# GPACConnector.net
KiCad netlist of a schematic drawn in Altium Designer
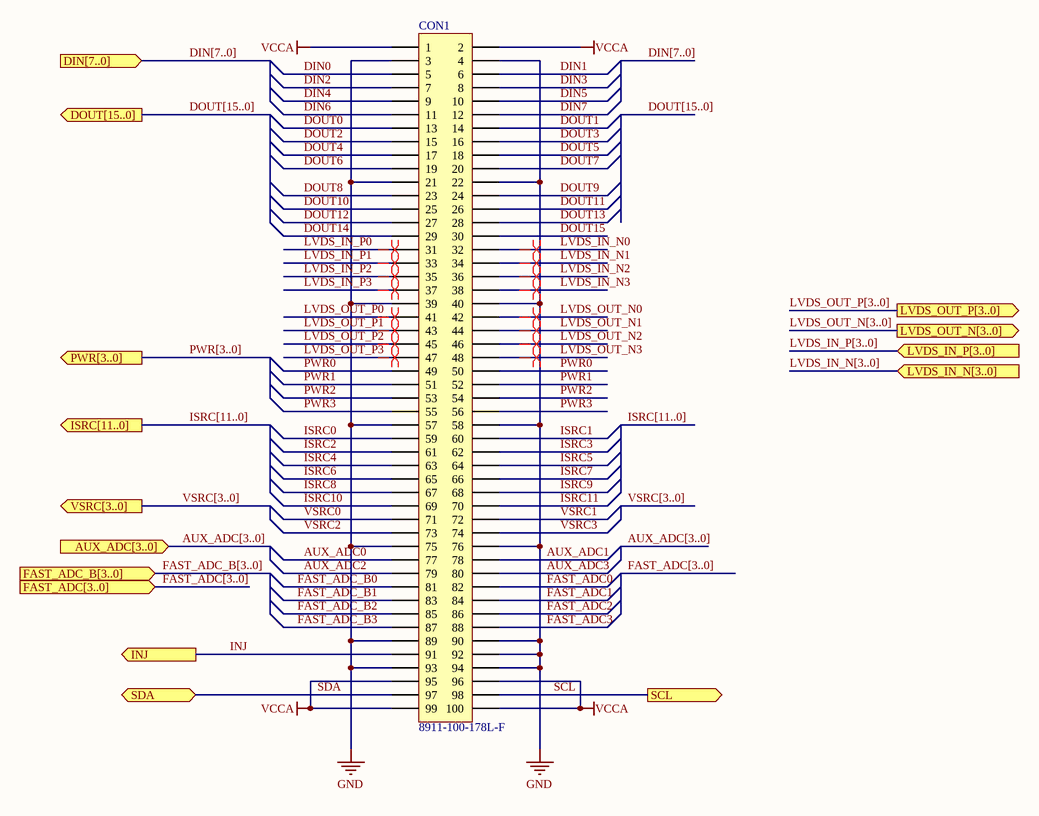
[diagram p0: GPACConnector.SchDoc]

(export (version "E")
  (design (tool "Eeschema 10.0.6"))
  (components
    (comp (ref "CON1")
      (value "-")
      (footprint "KEL 8911-100-178L-F, PLUG")
      (description "KEL 8911 100 pin board to board connector")
      (fields (field (name "TYPE_1") "8911-100-178L-F") (field (name "PUBLISHER") "Silab J.S."))
      (libsource (lib "Silab_Lib") (part "CON KEL 8911, male"))
    )
  )
  (nets
    (net (code "1") (name "/AUX_ADC0") (class "Default")
      (node (ref "CON1") (pin "77") (pinfunction "77_77") (pintype "passive"))
    )
    (net (code "2") (name "/AUX_ADC1") (class "Default")
      (node (ref "CON1") (pin "78") (pinfunction "78_78") (pintype "passive"))
    )
    (net (code "3") (name "/AUX_ADC2") (class "Default")
      (node (ref "CON1") (pin "79") (pinfunction "79_79") (pintype "passive"))
    )
    (net (code "4") (name "/AUX_ADC3") (class "Default")
      (node (ref "CON1") (pin "80") (pinfunction "80_80") (pintype "passive"))
    )
    (net (code "6") (name "/DIN0") (class "Default")
      (node (ref "CON1") (pin "5") (pinfunction "5_5") (pintype "passive"))
    )
    (net (code "7") (name "/DIN1") (class "Default")
      (node (ref "CON1") (pin "6") (pinfunction "6_6") (pintype "passive"))
    )
    (net (code "8") (name "/DIN2") (class "Default")
      (node (ref "CON1") (pin "7") (pinfunction "7_7") (pintype "passive"))
    )
    (net (code "9") (name "/DIN3") (class "Default")
      (node (ref "CON1") (pin "8") (pinfunction "8_8") (pintype "passive"))
    )
    (net (code "10") (name "/DIN4") (class "Default")
      (node (ref "CON1") (pin "9") (pinfunction "9_9") (pintype "passive"))
    )
    (net (code "11") (name "/DIN5") (class "Default")
      (node (ref "CON1") (pin "10") (pinfunction "10_10") (pintype "passive"))
    )
    (net (code "12") (name "/DIN6") (class "Default")
      (node (ref "CON1") (pin "11") (pinfunction "11_11") (pintype "passive"))
    )
    (net (code "13") (name "/DIN7") (class "Default")
      (node (ref "CON1") (pin "12") (pinfunction "12_12") (pintype "passive"))
    )
    (net (code "15") (name "/DOUT0") (class "Default")
      (node (ref "CON1") (pin "13") (pinfunction "13_13") (pintype "passive"))
    )
    (net (code "16") (name "/DOUT1") (class "Default")
      (node (ref "CON1") (pin "14") (pinfunction "14_14") (pintype "passive"))
    )
    (net (code "17") (name "/DOUT2") (class "Default")
      (node (ref "CON1") (pin "15") (pinfunction "15_15") (pintype "passive"))
    )
    (net (code "18") (name "/DOUT3") (class "Default")
      (node (ref "CON1") (pin "16") (pinfunction "16_16") (pintype "passive"))
    )
    (net (code "19") (name "/DOUT4") (class "Default")
      (node (ref "CON1") (pin "17") (pinfunction "17_17") (pintype "passive"))
    )
    (net (code "20") (name "/DOUT5") (class "Default")
      (node (ref "CON1") (pin "18") (pinfunction "18_18") (pintype "passive"))
    )
    (net (code "21") (name "/DOUT6") (class "Default")
      (node (ref "CON1") (pin "19") (pinfunction "19_19") (pintype "passive"))
    )
    (net (code "22") (name "/DOUT7") (class "Default")
      (node (ref "CON1") (pin "20") (pinfunction "20_20") (pintype "passive"))
    )
    (net (code "23") (name "/DOUT8") (class "Default")
      (node (ref "CON1") (pin "23") (pinfunction "23_23") (pintype "passive"))
    )
    (net (code "24") (name "/DOUT9") (class "Default")
      (node (ref "CON1") (pin "24") (pinfunction "24_24") (pintype "passive"))
    )
    (net (code "25") (name "/DOUT10") (class "Default")
      (node (ref "CON1") (pin "25") (pinfunction "25_25") (pintype "passive"))
    )
    (net (code "26") (name "/DOUT11") (class "Default")
      (node (ref "CON1") (pin "26") (pinfunction "26_26") (pintype "passive"))
    )
    (net (code "27") (name "/DOUT12") (class "Default")
      (node (ref "CON1") (pin "27") (pinfunction "27_27") (pintype "passive"))
    )
    (net (code "28") (name "/DOUT13") (class "Default")
      (node (ref "CON1") (pin "28") (pinfunction "28_28") (pintype "passive"))
    )
    (net (code "29") (name "/DOUT14") (class "Default")
      (node (ref "CON1") (pin "29") (pinfunction "29_29") (pintype "passive"))
    )
    (net (code "30") (name "/DOUT15") (class "Default")
      (node (ref "CON1") (pin "30") (pinfunction "30_30") (pintype "passive"))
    )
    (net (code "32") (name "/FAST_ADC0") (class "Default")
      (node (ref "CON1") (pin "82") (pinfunction "82_82") (pintype "passive"))
    )
    (net (code "33") (name "/FAST_ADC1") (class "Default")
      (node (ref "CON1") (pin "84") (pinfunction "84_84") (pintype "passive"))
    )
    (net (code "34") (name "/FAST_ADC2") (class "Default")
      (node (ref "CON1") (pin "86") (pinfunction "86_86") (pintype "passive"))
    )
    (net (code "35") (name "/FAST_ADC3") (class "Default")
      (node (ref "CON1") (pin "88") (pinfunction "88_88") (pintype "passive"))
    )
    (net (code "37") (name "/FAST_ADC_B0") (class "Default")
      (node (ref "CON1") (pin "81") (pinfunction "81_81") (pintype "passive"))
    )
    (net (code "38") (name "/FAST_ADC_B1") (class "Default")
      (node (ref "CON1") (pin "83") (pinfunction "83_83") (pintype "passive"))
    )
    (net (code "39") (name "/FAST_ADC_B2") (class "Default")
      (node (ref "CON1") (pin "85") (pinfunction "85_85") (pintype "passive"))
    )
    (net (code "40") (name "/FAST_ADC_B3") (class "Default")
      (node (ref "CON1") (pin "87") (pinfunction "87_87") (pintype "passive"))
    )
    (net (code "42") (name "/INJ") (class "Default")
      (node (ref "CON1") (pin "91") (pinfunction "91_91") (pintype "passive"))
    )
    (net (code "43") (name "/ISRC0") (class "Default")
      (node (ref "CON1") (pin "59") (pinfunction "59_59") (pintype "passive"))
    )
    (net (code "44") (name "/ISRC1") (class "Default")
      (node (ref "CON1") (pin "60") (pinfunction "60_60") (pintype "passive"))
    )
    (net (code "45") (name "/ISRC2") (class "Default")
      (node (ref "CON1") (pin "61") (pinfunction "61_61") (pintype "passive"))
    )
    (net (code "46") (name "/ISRC3") (class "Default")
      (node (ref "CON1") (pin "62") (pinfunction "62_62") (pintype "passive"))
    )
    (net (code "47") (name "/ISRC4") (class "Default")
      (node (ref "CON1") (pin "63") (pinfunction "63_63") (pintype "passive"))
    )
    (net (code "48") (name "/ISRC5") (class "Default")
      (node (ref "CON1") (pin "64") (pinfunction "64_64") (pintype "passive"))
    )
    (net (code "49") (name "/ISRC6") (class "Default")
      (node (ref "CON1") (pin "65") (pinfunction "65_65") (pintype "passive"))
    )
    (net (code "50") (name "/ISRC7") (class "Default")
      (node (ref "CON1") (pin "66") (pinfunction "66_66") (pintype "passive"))
    )
    (net (code "51") (name "/ISRC8") (class "Default")
      (node (ref "CON1") (pin "67") (pinfunction "67_67") (pintype "passive"))
    )
    (net (code "52") (name "/ISRC9") (class "Default")
      (node (ref "CON1") (pin "68") (pinfunction "68_68") (pintype "passive"))
    )
    (net (code "53") (name "/ISRC10") (class "Default")
      (node (ref "CON1") (pin "69") (pinfunction "69_69") (pintype "passive"))
    )
    (net (code "54") (name "/ISRC11") (class "Default")
      (node (ref "CON1") (pin "70") (pinfunction "70_70") (pintype "passive"))
    )
    (net (code "56") (name "/LVDS_IN_N0") (class "Default")
      (node (ref "CON1") (pin "32") (pinfunction "32_32") (pintype "passive"))
    )
    (net (code "57") (name "/LVDS_IN_N1") (class "Default")
      (node (ref "CON1") (pin "34") (pinfunction "34_34") (pintype "passive"))
    )
    (net (code "58") (name "/LVDS_IN_N2") (class "Default")
      (node (ref "CON1") (pin "36") (pinfunction "36_36") (pintype "passive"))
    )
    (net (code "59") (name "/LVDS_IN_N3") (class "Default")
      (node (ref "CON1") (pin "38") (pinfunction "38_38") (pintype "passive"))
    )
    (net (code "61") (name "/LVDS_IN_P0") (class "Default")
      (node (ref "CON1") (pin "31") (pinfunction "31_31") (pintype "passive"))
    )
    (net (code "62") (name "/LVDS_IN_P1") (class "Default")
      (node (ref "CON1") (pin "33") (pinfunction "33_33") (pintype "passive"))
    )
    (net (code "63") (name "/LVDS_IN_P2") (class "Default")
      (node (ref "CON1") (pin "35") (pinfunction "35_35") (pintype "passive"))
    )
    (net (code "64") (name "/LVDS_IN_P3") (class "Default")
      (node (ref "CON1") (pin "37") (pinfunction "37_37") (pintype "passive"))
    )
    (net (code "66") (name "/LVDS_OUT_N0") (class "Default")
      (node (ref "CON1") (pin "42") (pinfunction "42_42") (pintype "passive"))
    )
    (net (code "67") (name "/LVDS_OUT_N1") (class "Default")
      (node (ref "CON1") (pin "44") (pinfunction "44_44") (pintype "passive"))
    )
    (net (code "68") (name "/LVDS_OUT_N2") (class "Default")
      (node (ref "CON1") (pin "46") (pinfunction "46_46") (pintype "passive"))
    )
    (net (code "69") (name "/LVDS_OUT_N3") (class "Default")
      (node (ref "CON1") (pin "48") (pinfunction "48_48") (pintype "passive"))
    )
    (net (code "71") (name "/LVDS_OUT_P0") (class "Default")
      (node (ref "CON1") (pin "41") (pinfunction "41_41") (pintype "passive"))
    )
    (net (code "72") (name "/LVDS_OUT_P1") (class "Default")
      (node (ref "CON1") (pin "43") (pinfunction "43_43") (pintype "passive"))
    )
    (net (code "73") (name "/LVDS_OUT_P2") (class "Default")
      (node (ref "CON1") (pin "45") (pinfunction "45_45") (pintype "passive"))
    )
    (net (code "74") (name "/LVDS_OUT_P3") (class "Default")
      (node (ref "CON1") (pin "47") (pinfunction "47_47") (pintype "passive"))
    )
    (net (code "76") (name "/PWR0") (class "Default")
      (node (ref "CON1") (pin "49") (pinfunction "49_49") (pintype "passive"))
      (node (ref "CON1") (pin "50") (pinfunction "50_50") (pintype "passive"))
    )
    (net (code "77") (name "/PWR1") (class "Default")
      (node (ref "CON1") (pin "51") (pinfunction "51_51") (pintype "passive"))
      (node (ref "CON1") (pin "52") (pinfunction "52_52") (pintype "passive"))
    )
    (net (code "78") (name "/PWR2") (class "Default")
      (node (ref "CON1") (pin "53") (pinfunction "53_53") (pintype "passive"))
      (node (ref "CON1") (pin "54") (pinfunction "54_54") (pintype "passive"))
    )
    (net (code "79") (name "/PWR3") (class "Default")
      (node (ref "CON1") (pin "55") (pinfunction "55_55") (pintype "passive"))
      (node (ref "CON1") (pin "56") (pinfunction "56_56") (pintype "passive"))
    )
    (net (code "81") (name "/SCL") (class "Default")
      (node (ref "CON1") (pin "98") (pinfunction "98_98") (pintype "passive"))
    )
    (net (code "82") (name "/SDA") (class "Default")
      (node (ref "CON1") (pin "97") (pinfunction "97_97") (pintype "passive"))
    )
    (net (code "83") (name "/VSRC0") (class "Default")
      (node (ref "CON1") (pin "71") (pinfunction "71_71") (pintype "passive"))
    )
    (net (code "84") (name "/VSRC1") (class "Default")
      (node (ref "CON1") (pin "72") (pinfunction "72_72") (pintype "passive"))
    )
    (net (code "85") (name "/VSRC2") (class "Default")
      (node (ref "CON1") (pin "73") (pinfunction "73_73") (pintype "passive"))
    )
    (net (code "86") (name "/VSRC3") (class "Default")
      (node (ref "CON1") (pin "74") (pinfunction "74_74") (pintype "passive"))
    )
    (net (code "88") (name "GND") (class "Default")
      (node (ref "CON1") (pin "21") (pinfunction "21_21") (pintype "passive"))
      (node (ref "CON1") (pin "22") (pinfunction "22_22") (pintype "passive"))
      (node (ref "CON1") (pin "3") (pinfunction "3_3") (pintype "passive"))
      (node (ref "CON1") (pin "39") (pinfunction "39_39") (pintype "passive"))
      (node (ref "CON1") (pin "4") (pinfunction "4_4") (pintype "passive"))
      (node (ref "CON1") (pin "40") (pinfunction "40_40") (pintype "passive"))
      (node (ref "CON1") (pin "57") (pinfunction "57_57") (pintype "passive"))
      (node (ref "CON1") (pin "58") (pinfunction "58_58") (pintype "passive"))
      (node (ref "CON1") (pin "75") (pinfunction "75_75") (pintype "passive"))
      (node (ref "CON1") (pin "76") (pinfunction "76_76") (pintype "passive"))
      (node (ref "CON1") (pin "89") (pinfunction "89_89") (pintype "passive"))
      (node (ref "CON1") (pin "90") (pinfunction "90_90") (pintype "passive"))
      (node (ref "CON1") (pin "92") (pinfunction "92_92") (pintype "passive"))
      (node (ref "CON1") (pin "93") (pinfunction "93_93") (pintype "passive"))
      (node (ref "CON1") (pin "94") (pinfunction "94_94") (pintype "passive"))
    )
    (net (code "89") (name "VCCA") (class "Default")
      (node (ref "CON1") (pin "1") (pinfunction "1_1") (pintype "passive"))
      (node (ref "CON1") (pin "100") (pinfunction "100_100") (pintype "passive"))
      (node (ref "CON1") (pin "2") (pinfunction "2_2") (pintype "passive"))
      (node (ref "CON1") (pin "95") (pinfunction "95_95") (pintype "passive"))
      (node (ref "CON1") (pin "96") (pinfunction "96_96") (pintype "passive"))
      (node (ref "CON1") (pin "99") (pinfunction "99_99") (pintype "passive"))
    )
  )
)
